# Flasche_v1.net
KiCad netlist of a schematic drawn in EAGLE
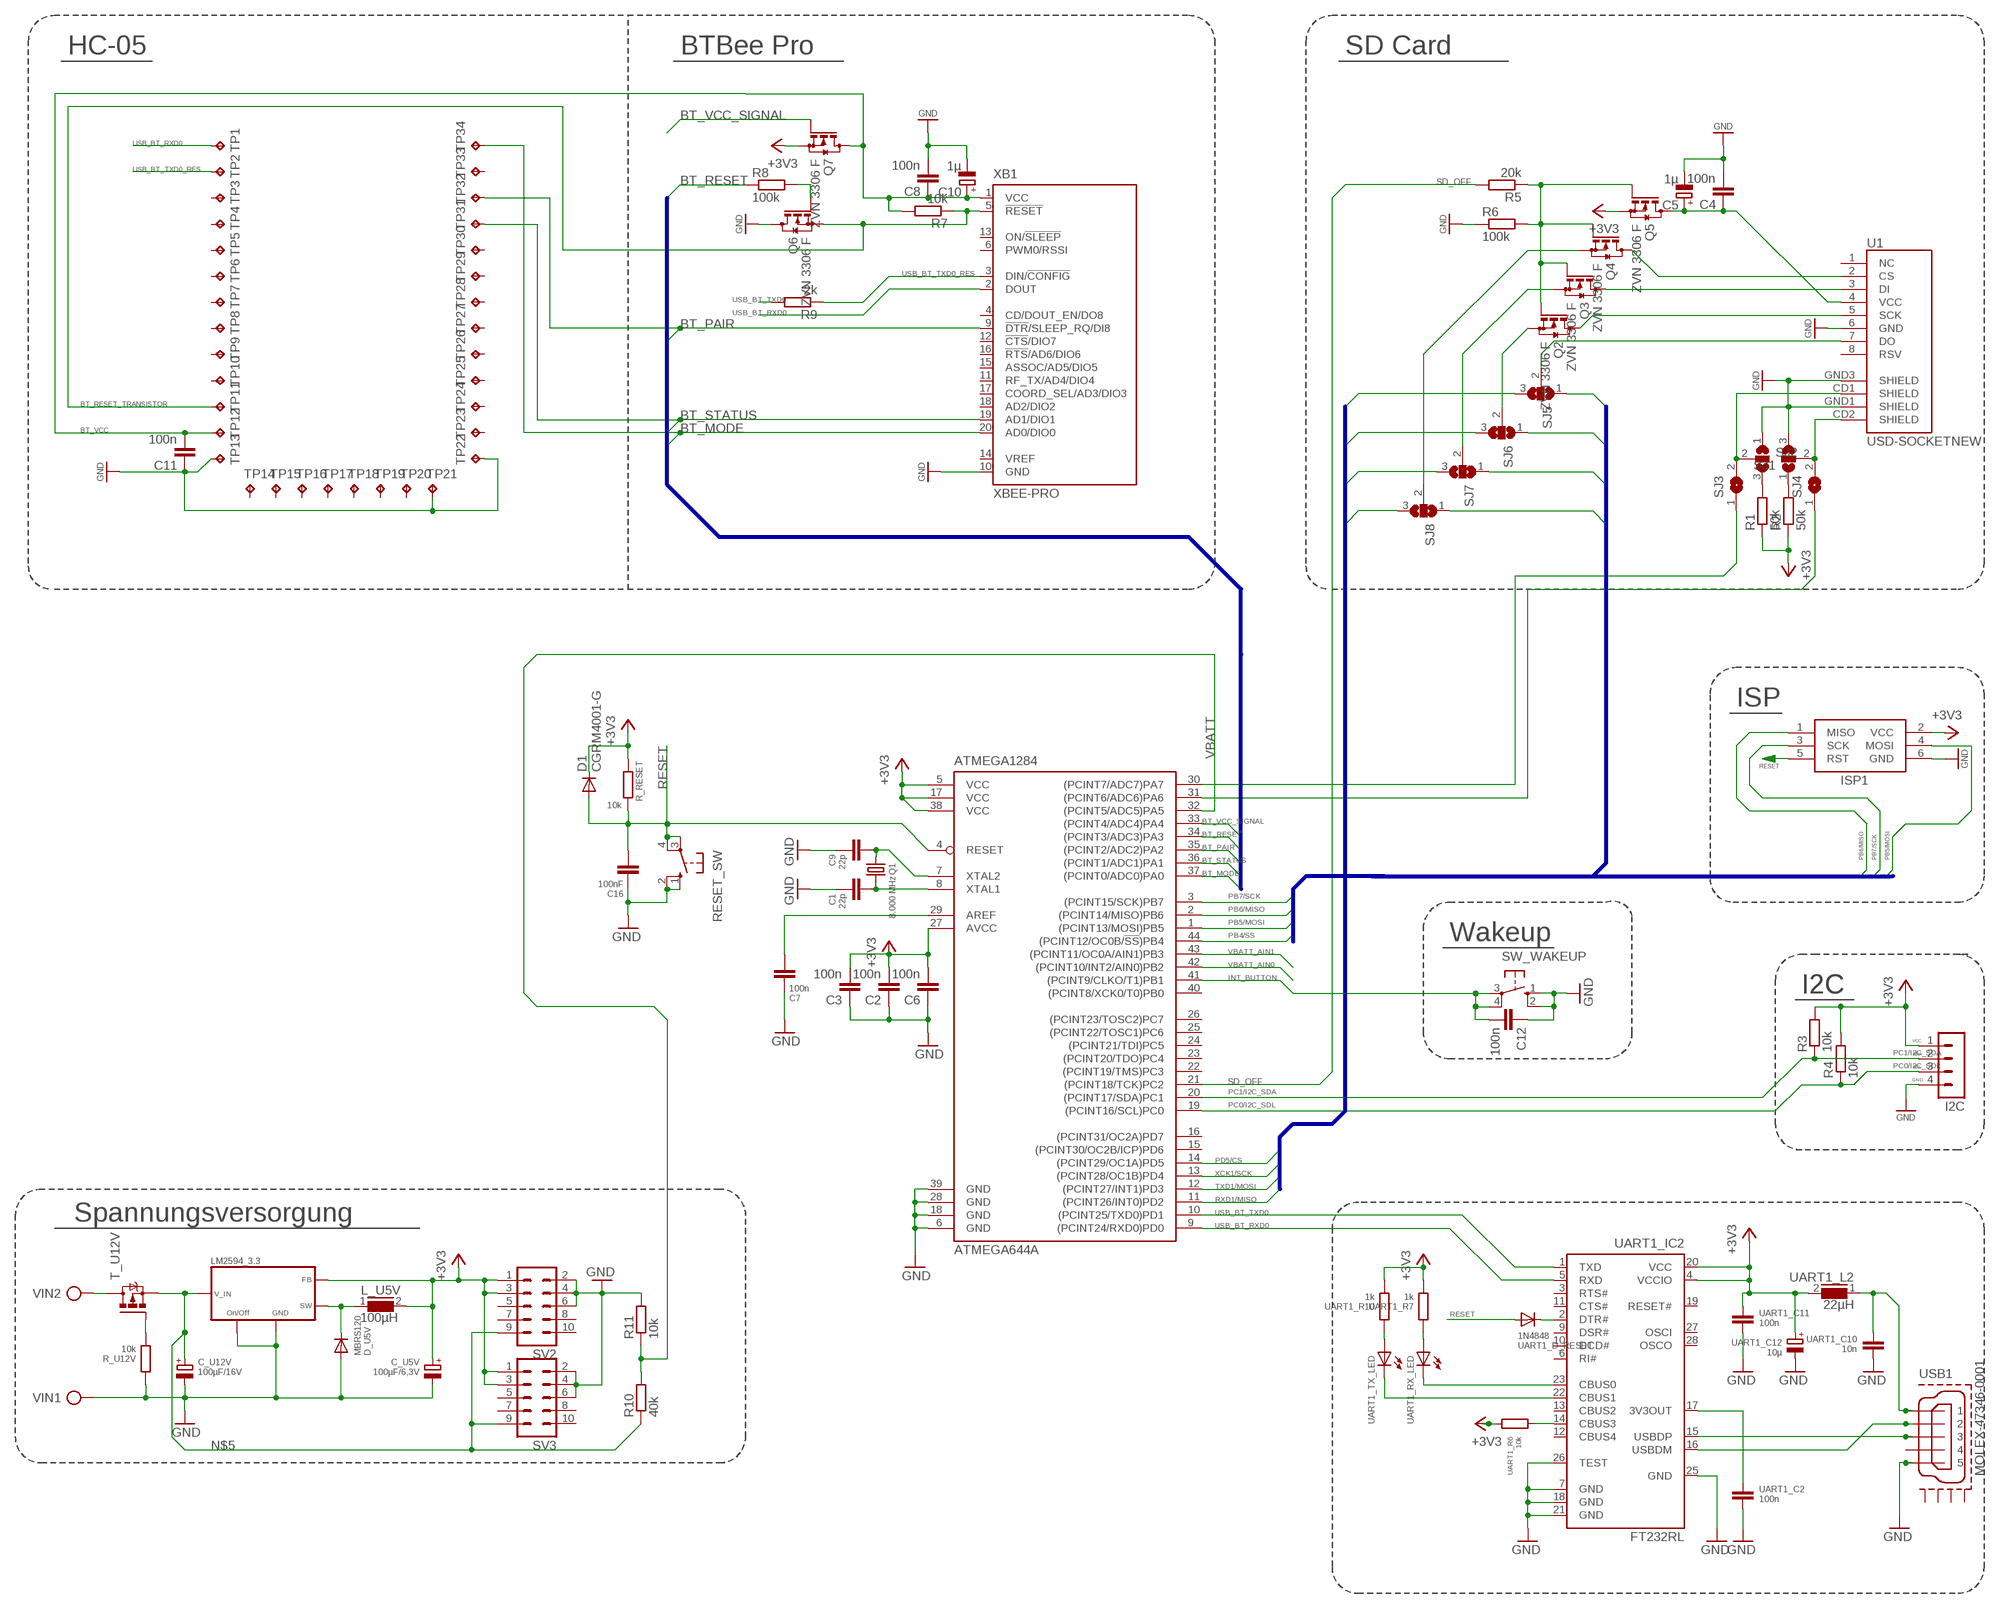
[diagram p0: schematic, sheet 1]

(export (version "E")
  (design (tool "Eeschema 10.0.6"))
  (components
    (comp (ref "ATMEGA1284")
      (value "ATMEGA644A")
      (footprint "eagle-import:TQFP44")
      (fields (field (name "MPN") "ATMEGA644PV-10AU"))
      (libsource (lib "eagle-import") (part "ATMEGA644A"))
    )
    (comp (ref "C1")
      (value "22p")
      (footprint "eagle-import:C0805")
      (libsource (lib "eagle-import") (part "C-0805"))
    )
    (comp (ref "C2")
      (value "100n")
      (footprint "eagle-import:C0805")
      (libsource (lib "eagle-import") (part "C-0805"))
    )
    (comp (ref "C3")
      (value "100n")
      (footprint "eagle-import:C0805")
      (libsource (lib "eagle-import") (part "C-0805"))
    )
    (comp (ref "C4")
      (value "100n")
      (footprint "eagle-import:C0805")
      (libsource (lib "eagle-import") (part "C-0805"))
    )
    (comp (ref "C5")
      (value "1µ")
      (footprint "eagle-import:SMC_D")
      (libsource (lib "eagle-import") (part "rcl_CPOL-EUSMCD"))
    )
    (comp (ref "C6")
      (value "100n")
      (footprint "eagle-import:C0805")
      (libsource (lib "eagle-import") (part "C-0805"))
    )
    (comp (ref "C7")
      (value "100n")
      (footprint "eagle-import:C0805")
      (libsource (lib "eagle-import") (part "C-0805"))
    )
    (comp (ref "C8")
      (value "100n")
      (footprint "eagle-import:C0805")
      (libsource (lib "eagle-import") (part "C-0805"))
    )
    (comp (ref "C9")
      (value "22p")
      (footprint "eagle-import:C0805")
      (libsource (lib "eagle-import") (part "C-0805"))
    )
    (comp (ref "C10")
      (value "1µ")
      (footprint "eagle-import:SMC_D")
      (libsource (lib "eagle-import") (part "rcl_CPOL-EUSMCD"))
    )
    (comp (ref "C11")
      (value "100n")
      (footprint "eagle-import:C0805")
      (libsource (lib "eagle-import") (part "C-0805"))
    )
    (comp (ref "C12")
      (value "100n")
      (footprint "eagle-import:C0805")
      (libsource (lib "eagle-import") (part "C-0805"))
    )
    (comp (ref "C16")
      (value "100nF")
      (footprint "eagle-import:C0805")
      (libsource (lib "eagle-import") (part "C-0805"))
    )
    (comp (ref "C_U5V")
      (value "100µF/6,3V")
      (footprint "eagle-import:SMC_D")
      (libsource (lib "eagle-import") (part "CPOL-EUSMCD"))
    )
    (comp (ref "C_U12V")
      (value "100µF/16V")
      (footprint "eagle-import:SMC_D")
      (libsource (lib "eagle-import") (part "CPOL-EUSMCD"))
    )
    (comp (ref "D1")
      (value "CGRM4001-G")
      (footprint "eagle-import:SOD-123_MINI-SMA")
      (libsource (lib "eagle-import") (part "CGRM400-G1"))
    )
    (comp (ref "D_U5V")
      (value "MBRS120")
      (footprint "eagle-import:SMB")
      (libsource (lib "eagle-import") (part "D_SMB"))
    )
    (comp (ref "I2C")
      (value "MA04-1")
      (footprint "eagle-import:MA04-1")
      (libsource (lib "eagle-import") (part "MA04-1"))
    )
    (comp (ref "ISP1")
      (value "AVRISP-6")
      (footprint "eagle-import:AVRISP")
      (libsource (lib "eagle-import") (part "AVRISP-6"))
    )
    (comp (ref "LM2594_3.3")
      (value "LM2594")
      (footprint "eagle-import:SO08")
      (libsource (lib "eagle-import") (part "LM2594"))
    )
    (comp (ref "L_U5V")
      (value "100µH")
      (footprint "eagle-import:PISM")
      (libsource (lib "eagle-import") (part "L_PISM"))
    )
    (comp (ref "Q1")
      (value "8.000 MHz")
      (footprint "eagle-import:HC18U-V")
      (libsource (lib "eagle-import") (part "CRYSTALHC18U-V"))
    )
    (comp (ref "Q2")
      (value "ZVN 3306 F")
      (footprint "eagle-import:SOT23")
      (libsource (lib "eagle-import") (part "BSS123"))
    )
    (comp (ref "Q3")
      (value "ZVN 3306 F")
      (footprint "eagle-import:SOT23")
      (libsource (lib "eagle-import") (part "BSS123"))
    )
    (comp (ref "Q4")
      (value "ZVN 3306 F")
      (footprint "eagle-import:SOT23")
      (libsource (lib "eagle-import") (part "BSS123"))
    )
    (comp (ref "Q5")
      (value "ZVN 3306 F")
      (footprint "eagle-import:SOT23")
      (libsource (lib "eagle-import") (part "BSS123"))
    )
    (comp (ref "Q6")
      (value "ZVN 3306 F")
      (footprint "eagle-import:SOT23")
      (libsource (lib "eagle-import") (part "BSS123"))
    )
    (comp (ref "Q7")
      (value "ZVN 3306 F")
      (footprint "eagle-import:SOT23")
      (libsource (lib "eagle-import") (part "BSS123"))
    )
    (comp (ref "R1")
      (value "50k")
      (footprint "eagle-import:M1206")
      (libsource (lib "eagle-import") (part "R-EU_M1206"))
    )
    (comp (ref "R2")
      (value "50k")
      (footprint "eagle-import:M1206")
      (libsource (lib "eagle-import") (part "R-EU_M1206"))
    )
    (comp (ref "R3")
      (value "10k")
      (footprint "eagle-import:M1206")
      (libsource (lib "eagle-import") (part "R-EU_M1206"))
    )
    (comp (ref "R4")
      (value "10k")
      (footprint "eagle-import:M1206")
      (libsource (lib "eagle-import") (part "R-EU_M1206"))
    )
    (comp (ref "R5")
      (value "20k")
      (footprint "eagle-import:M1206")
      (libsource (lib "eagle-import") (part "R-EU_M1206"))
    )
    (comp (ref "R6")
      (value "100k")
      (footprint "eagle-import:M1206")
      (libsource (lib "eagle-import") (part "R-EU_M1206"))
    )
    (comp (ref "R7")
      (value "10k")
      (footprint "eagle-import:M1206")
      (libsource (lib "eagle-import") (part "R-EU_M1206"))
    )
    (comp (ref "R8")
      (value "100k")
      (footprint "eagle-import:M1206")
      (libsource (lib "eagle-import") (part "R-EU_M1206"))
    )
    (comp (ref "R9")
      (value "2k")
      (footprint "eagle-import:M1206")
      (libsource (lib "eagle-import") (part "R-EU_M1206"))
    )
    (comp (ref "R10")
      (value "40k")
      (footprint "eagle-import:M1206")
      (libsource (lib "eagle-import") (part "R-EU_M1206"))
    )
    (comp (ref "R11")
      (value "10k")
      (footprint "eagle-import:M1206")
      (libsource (lib "eagle-import") (part "R-EU_M1206"))
    )
    (comp (ref "RESET_SW")
      (value "10-XX")
      (footprint "eagle-import:B3F-10XX")
      (fields (field (name "MPN") "B3F-1000"))
      (libsource (lib "eagle-import") (part "10-XX"))
    )
    (comp (ref "R_RESET")
      (value "10k")
      (footprint "eagle-import:R0805")
      (libsource (lib "eagle-import") (part "R-R0805"))
    )
    (comp (ref "R_U12V")
      (value "10k")
      (footprint "eagle-import:R0805")
      (libsource (lib "eagle-import") (part "R-R0805"))
    )
    (comp (ref "SJ1")
      (value "SJ2W")
      (footprint "eagle-import:SJ_2")
      (libsource (lib "eagle-import") (part "SJ2W"))
    )
    (comp (ref "SJ2")
      (value "SJ2W")
      (footprint "eagle-import:SJ_2")
      (libsource (lib "eagle-import") (part "SJ2W"))
    )
    (comp (ref "SJ3") (value "SJ") (footprint "eagle-import:SJ") (libsource (lib "eagle-import") (part "SJ")))
    (comp (ref "SJ4") (value "SJ") (footprint "eagle-import:SJ") (libsource (lib "eagle-import") (part "SJ")))
    (comp (ref "SJ5")
      (value "SJ2W")
      (footprint "eagle-import:SJ_2")
      (libsource (lib "eagle-import") (part "SJ2W"))
    )
    (comp (ref "SJ6")
      (value "SJ2W")
      (footprint "eagle-import:SJ_2")
      (libsource (lib "eagle-import") (part "SJ2W"))
    )
    (comp (ref "SJ7")
      (value "SJ2W")
      (footprint "eagle-import:SJ_2")
      (libsource (lib "eagle-import") (part "SJ2W"))
    )
    (comp (ref "SJ8")
      (value "SJ2W")
      (footprint "eagle-import:SJ_2")
      (libsource (lib "eagle-import") (part "SJ2W"))
    )
    (comp (ref "SV2")
      (value "ML10L")
      (footprint "eagle-import:ML10L")
      (libsource (lib "eagle-import") (part "ML10L"))
    )
    (comp (ref "SV3")
      (value "ML10L")
      (footprint "eagle-import:ML10L")
      (libsource (lib "eagle-import") (part "ML10L"))
    )
    (comp (ref "SW_WAKEUP")
      (value "10-XX")
      (footprint "eagle-import:B3F-10XX")
      (fields (field (name "MPN") "B3F-1000"))
      (libsource (lib "eagle-import") (part "10-XX"))
    )
    (comp (ref "TP1")
      (value "TPTP06SQ")
      (footprint "eagle-import:TP06SQ")
      (libsource (lib "eagle-import") (part "TPTP06SQ"))
    )
    (comp (ref "TP2")
      (value "TPTP06SQ")
      (footprint "eagle-import:TP06SQ")
      (libsource (lib "eagle-import") (part "TPTP06SQ"))
    )
    (comp (ref "TP3")
      (value "TPTP06SQ")
      (footprint "eagle-import:TP06SQ")
      (libsource (lib "eagle-import") (part "TPTP06SQ"))
    )
    (comp (ref "TP4")
      (value "TPTP06SQ")
      (footprint "eagle-import:TP06SQ")
      (libsource (lib "eagle-import") (part "TPTP06SQ"))
    )
    (comp (ref "TP5")
      (value "TPTP06SQ")
      (footprint "eagle-import:TP06SQ")
      (libsource (lib "eagle-import") (part "TPTP06SQ"))
    )
    (comp (ref "TP6")
      (value "TPTP06SQ")
      (footprint "eagle-import:TP06SQ")
      (libsource (lib "eagle-import") (part "TPTP06SQ"))
    )
    (comp (ref "TP7")
      (value "TPTP06SQ")
      (footprint "eagle-import:TP06SQ")
      (libsource (lib "eagle-import") (part "TPTP06SQ"))
    )
    (comp (ref "TP8")
      (value "TPTP06SQ")
      (footprint "eagle-import:TP06SQ")
      (libsource (lib "eagle-import") (part "TPTP06SQ"))
    )
    (comp (ref "TP9")
      (value "TPTP06SQ")
      (footprint "eagle-import:TP06SQ")
      (libsource (lib "eagle-import") (part "TPTP06SQ"))
    )
    (comp (ref "TP10")
      (value "TPTP06SQ")
      (footprint "eagle-import:TP06SQ")
      (libsource (lib "eagle-import") (part "TPTP06SQ"))
    )
    (comp (ref "TP11")
      (value "TPTP06SQ")
      (footprint "eagle-import:TP06SQ")
      (libsource (lib "eagle-import") (part "TPTP06SQ"))
    )
    (comp (ref "TP12")
      (value "TPTP06SQ")
      (footprint "eagle-import:TP06SQ")
      (libsource (lib "eagle-import") (part "TPTP06SQ"))
    )
    (comp (ref "TP13")
      (value "TPTP06SQ")
      (footprint "eagle-import:TP06SQ")
      (libsource (lib "eagle-import") (part "TPTP06SQ"))
    )
    (comp (ref "TP14")
      (value "TPTP06SQ")
      (footprint "eagle-import:TP06SQ")
      (libsource (lib "eagle-import") (part "TPTP06SQ"))
    )
    (comp (ref "TP15")
      (value "TPTP06SQ")
      (footprint "eagle-import:TP06SQ")
      (libsource (lib "eagle-import") (part "TPTP06SQ"))
    )
    (comp (ref "TP16")
      (value "TPTP06SQ")
      (footprint "eagle-import:TP06SQ")
      (libsource (lib "eagle-import") (part "TPTP06SQ"))
    )
    (comp (ref "TP17")
      (value "TPTP06SQ")
      (footprint "eagle-import:TP06SQ")
      (libsource (lib "eagle-import") (part "TPTP06SQ"))
    )
    (comp (ref "TP18")
      (value "TPTP06SQ")
      (footprint "eagle-import:TP06SQ")
      (libsource (lib "eagle-import") (part "TPTP06SQ"))
    )
    (comp (ref "TP19")
      (value "TPTP06SQ")
      (footprint "eagle-import:TP06SQ")
      (libsource (lib "eagle-import") (part "TPTP06SQ"))
    )
    (comp (ref "TP20")
      (value "TPTP06SQ")
      (footprint "eagle-import:TP06SQ")
      (libsource (lib "eagle-import") (part "TPTP06SQ"))
    )
    (comp (ref "TP21")
      (value "TPTP06SQ")
      (footprint "eagle-import:TP06SQ")
      (libsource (lib "eagle-import") (part "TPTP06SQ"))
    )
    (comp (ref "TP22")
      (value "TPTP06SQ")
      (footprint "eagle-import:TP06SQ")
      (libsource (lib "eagle-import") (part "TPTP06SQ"))
    )
    (comp (ref "TP23")
      (value "TPTP06SQ")
      (footprint "eagle-import:TP06SQ")
      (libsource (lib "eagle-import") (part "TPTP06SQ"))
    )
    (comp (ref "TP24")
      (value "TPTP06SQ")
      (footprint "eagle-import:TP06SQ")
      (libsource (lib "eagle-import") (part "TPTP06SQ"))
    )
    (comp (ref "TP25")
      (value "TPTP06SQ")
      (footprint "eagle-import:TP06SQ")
      (libsource (lib "eagle-import") (part "TPTP06SQ"))
    )
    (comp (ref "TP26")
      (value "TPTP06SQ")
      (footprint "eagle-import:TP06SQ")
      (libsource (lib "eagle-import") (part "TPTP06SQ"))
    )
    (comp (ref "TP27")
      (value "TPTP06SQ")
      (footprint "eagle-import:TP06SQ")
      (libsource (lib "eagle-import") (part "TPTP06SQ"))
    )
    (comp (ref "TP28")
      (value "TPTP06SQ")
      (footprint "eagle-import:TP06SQ")
      (libsource (lib "eagle-import") (part "TPTP06SQ"))
    )
    (comp (ref "TP29")
      (value "TPTP06SQ")
      (footprint "eagle-import:TP06SQ")
      (libsource (lib "eagle-import") (part "TPTP06SQ"))
    )
    (comp (ref "TP30")
      (value "TPTP06SQ")
      (footprint "eagle-import:TP06SQ")
      (libsource (lib "eagle-import") (part "TPTP06SQ"))
    )
    (comp (ref "TP31")
      (value "TPTP06SQ")
      (footprint "eagle-import:TP06SQ")
      (libsource (lib "eagle-import") (part "TPTP06SQ"))
    )
    (comp (ref "TP32")
      (value "TPTP06SQ")
      (footprint "eagle-import:TP06SQ")
      (libsource (lib "eagle-import") (part "TPTP06SQ"))
    )
    (comp (ref "TP33")
      (value "TPTP06SQ")
      (footprint "eagle-import:TP06SQ")
      (libsource (lib "eagle-import") (part "TPTP06SQ"))
    )
    (comp (ref "TP34")
      (value "TPTP06SQ")
      (footprint "eagle-import:TP06SQ")
      (libsource (lib "eagle-import") (part "TPTP06SQ"))
    )
    (comp (ref "T_U12V")
      (value "MOS_P_SOT23_GDS")
      (footprint "eagle-import:SOT23")
      (libsource (lib "eagle-import") (part "MOS_P_SOT23_GDS"))
    )
    (comp (ref "U1")
      (value "USD-SOCKETNEW")
      (footprint "eagle-import:MICRO-SD-SOCKET-PP")
      (libsource (lib "eagle-import") (part "USD-SOCKETNEW"))
    )
    (comp (ref "UART1_C2")
      (value "100n")
      (footprint "eagle-import:C0805")
      (libsource (lib "eagle-import") (part "C-EUC0805"))
    )
    (comp (ref "UART1_C10")
      (value "10n")
      (footprint "eagle-import:C0805")
      (libsource (lib "eagle-import") (part "C-EUC0805"))
    )
    (comp (ref "UART1_C11")
      (value "100n")
      (footprint "eagle-import:C0805")
      (libsource (lib "eagle-import") (part "C-EUC0805"))
    )
    (comp (ref "UART1_C12")
      (value "10µ")
      (footprint "eagle-import:SMC_D")
      (libsource (lib "eagle-import") (part "CPOL-EUSMCD"))
    )
    (comp (ref "UART1_D_RESET")
      (value "1N4848")
      (footprint "eagle-import:MINIMELF")
      (libsource (lib "eagle-import") (part "D_MINIMELF"))
    )
    (comp (ref "UART1_IC2")
      (value "FT232RL")
      (footprint "eagle-import:SSOP28")
      (libsource (lib "eagle-import") (part "FT232RL"))
    )
    (comp (ref "UART1_L2")
      (value "22µH")
      (footprint "eagle-import:PIS2408")
      (libsource (lib "eagle-import") (part "L_PIS2408"))
    )
    (comp (ref "UART1_R6")
      (value "10k")
      (footprint "eagle-import:R0805")
      (libsource (lib "eagle-import") (part "R-EU_R0805"))
    )
    (comp (ref "UART1_R7")
      (value "1k")
      (footprint "eagle-import:R0805")
      (libsource (lib "eagle-import") (part "R-R0805"))
    )
    (comp (ref "UART1_R10")
      (value "1k")
      (footprint "eagle-import:R0805")
      (libsource (lib "eagle-import") (part "R-R0805"))
    )
    (comp (ref "UART1_RX_LED")
      (value "LEDCHIPLED_0805")
      (footprint "eagle-import:CHIPLED_0805")
      (libsource (lib "eagle-import") (part "LEDCHIPLED_0805"))
    )
    (comp (ref "UART1_TX_LED")
      (value "LEDCHIPLED_0805")
      (footprint "eagle-import:CHIPLED_0805")
      (libsource (lib "eagle-import") (part "LEDCHIPLED_0805"))
    )
    (comp (ref "USB1")
      (value "MOLEX-47346-0001")
      (footprint "eagle-import:MOLEX-47364-0001")
      (libsource (lib "eagle-import") (part "MOLEX-47346-0001"))
    )
    (comp (ref "VIN")
      (value "AK350/2")
      (footprint "eagle-import:AK350_2")
      (libsource (lib "eagle-import") (part "AK350/2"))
    )
    (comp (ref "XB1")
      (value "XBEE-PRO")
      (footprint "eagle-import:XBEE-PRO")
      (fields (field (name "MPN") "XBP24-AWI-001"))
      (libsource (lib "eagle-import") (part "XBEE-PRO"))
    )
  )
  (nets
    (net (code "1") (name "+3V3") (class "Default")
      (node (ref "ATMEGA1284") (pin "17") (pinfunction "VCC_17") (pintype "power_in"))
      (node (ref "ATMEGA1284") (pin "27") (pinfunction "AVCC_27") (pintype "power_in"))
      (node (ref "ATMEGA1284") (pin "38") (pinfunction "VCC_38") (pintype "power_in"))
      (node (ref "ATMEGA1284") (pin "5") (pinfunction "VCC_5") (pintype "power_in"))
      (node (ref "C2") (pin "2") (pinfunction "2_2") (pintype "passive"))
      (node (ref "C3") (pin "2") (pinfunction "2_2") (pintype "passive"))
      (node (ref "C6") (pin "2") (pinfunction "2_2") (pintype "passive"))
      (node (ref "C_U5V") (pin "+") (pinfunction "+_+") (pintype "passive"))
      (node (ref "D1") (pin "C") (pinfunction "C_C") (pintype "passive"))
      (node (ref "I2C") (pin "1") (pinfunction "1_1") (pintype "passive"))
      (node (ref "ISP1") (pin "2") (pinfunction "VCC_2") (pintype "power_in"))
      (node (ref "LM2594_3.3") (pin "4") (pinfunction "FB_4") (pintype "passive"))
      (node (ref "L_U5V") (pin "2") (pinfunction "2_2") (pintype "passive"))
      (node (ref "Q5") (pin "2") (pinfunction "S_2") (pintype "passive"))
      (node (ref "Q7") (pin "2") (pinfunction "S_2") (pintype "passive"))
      (node (ref "R1") (pin "1") (pinfunction "1_1") (pintype "passive"))
      (node (ref "R2") (pin "1") (pinfunction "1_1") (pintype "passive"))
      (node (ref "R3") (pin "2") (pinfunction "2_2") (pintype "passive"))
      (node (ref "R4") (pin "2") (pinfunction "2_2") (pintype "passive"))
      (node (ref "R_RESET") (pin "2") (pinfunction "2_2") (pintype "passive"))
      (node (ref "SV2") (pin "1") (pinfunction "1_1") (pintype "passive"))
      (node (ref "SV2") (pin "3") (pinfunction "3_3") (pintype "passive"))
      (node (ref "SV3") (pin "1") (pinfunction "1_1") (pintype "passive"))
      (node (ref "SV3") (pin "3") (pinfunction "3_3") (pintype "passive"))
      (node (ref "UART1_C11") (pin "1") (pinfunction "1_1") (pintype "passive"))
      (node (ref "UART1_C12") (pin "+") (pinfunction "+_+") (pintype "passive"))
      (node (ref "UART1_IC2") (pin "20") (pinfunction "VCC_20") (pintype "input"))
      (node (ref "UART1_IC2") (pin "4") (pinfunction "VCCIO_4") (pintype "input"))
      (node (ref "UART1_L2") (pin "2") (pinfunction "2_2") (pintype "passive"))
      (node (ref "UART1_R10") (pin "1") (pinfunction "1_1") (pintype "passive"))
      (node (ref "UART1_R6") (pin "2") (pinfunction "2_2") (pintype "passive"))
      (node (ref "UART1_R7") (pin "1") (pinfunction "1_1") (pintype "passive"))
    )
    (net (code "2") (name "/BT_MODE") (class "Default")
      (node (ref "ATMEGA1284") (pin "37") (pinfunction "(PCINT0/ADC0)PA0_37") (pintype "bidirectional"))
      (node (ref "TP34") (pin "TP") (pinfunction "TP_TP") (pintype "input"))
      (node (ref "XB1") (pin "20") (pinfunction "AD0/DIO0_20") (pintype "bidirectional"))
    )
    (net (code "3") (name "/BT_PAIR") (class "Default")
      (node (ref "ATMEGA1284") (pin "35") (pinfunction "(PCINT2/ADC2)PA2_35") (pintype "bidirectional"))
      (node (ref "TP32") (pin "TP") (pinfunction "TP_TP") (pintype "input"))
      (node (ref "XB1") (pin "9") (pinfunction "~{DTR}/SLEEP_RQ/DI8_9") (pintype "bidirectional"))
    )
    (net (code "4") (name "/BT_RESET") (class "Default")
      (node (ref "ATMEGA1284") (pin "34") (pinfunction "(PCINT3/ADC3)PA3_34") (pintype "bidirectional"))
      (node (ref "R8") (pin "1") (pinfunction "1_1") (pintype "passive"))
    )
    (net (code "5") (name "/BT_RESET_TRANSISTOR") (class "Default")
      (node (ref "Q6") (pin "2") (pinfunction "S_2") (pintype "passive"))
      (node (ref "R7") (pin "1") (pinfunction "1_1") (pintype "passive"))
      (node (ref "TP11") (pin "TP") (pinfunction "TP_TP") (pintype "input"))
      (node (ref "XB1") (pin "5") (pinfunction "~{RESET}_5") (pintype "input"))
    )
    (net (code "6") (name "/BT_STATUS") (class "Default")
      (node (ref "ATMEGA1284") (pin "36") (pinfunction "(PCINT1/ADC1)PA1_36") (pintype "bidirectional"))
      (node (ref "TP31") (pin "TP") (pinfunction "TP_TP") (pintype "input"))
      (node (ref "XB1") (pin "19") (pinfunction "AD1/DIO1_19") (pintype "bidirectional"))
    )
    (net (code "7") (name "/BT_VCC") (class "Default")
      (node (ref "C10") (pin "+") (pinfunction "+_+") (pintype "passive"))
      (node (ref "C11") (pin "2") (pinfunction "2_2") (pintype "passive"))
      (node (ref "C8") (pin "1") (pinfunction "1_1") (pintype "passive"))
      (node (ref "Q7") (pin "3") (pinfunction "D_3") (pintype "passive"))
      (node (ref "R7") (pin "2") (pinfunction "2_2") (pintype "passive"))
      (node (ref "TP12") (pin "TP") (pinfunction "TP_TP") (pintype "input"))
      (node (ref "XB1") (pin "1") (pinfunction "VCC_1") (pintype "power_in"))
    )
    (net (code "8") (name "/BT_VCC_SIGNAL") (class "Default")
      (node (ref "ATMEGA1284") (pin "33") (pinfunction "(PCINT4/ADC4)PA4_33") (pintype "bidirectional"))
      (node (ref "Q7") (pin "1") (pinfunction "G_1") (pintype "passive"))
    )
    (net (code "9") (name "/INT_BUTTON") (class "Default")
      (node (ref "ATMEGA1284") (pin "41") (pinfunction "(PCINT9/CLKO/T1)PB1_41") (pintype "bidirectional"))
      (node (ref "C12") (pin "2") (pinfunction "2_2") (pintype "passive"))
      (node (ref "SW_WAKEUP") (pin "3") (pinfunction "P_3") (pintype "passive"))
      (node (ref "SW_WAKEUP") (pin "4") (pinfunction "P1_4") (pintype "passive"))
    )
    (net (code "10") (name "/N$5") (class "Default")
      (node (ref "C_U12V") (pin "+") (pinfunction "+_+") (pintype "passive"))
      (node (ref "LM2594_3.3") (pin "7") (pinfunction "IN_7") (pintype "power_in"))
      (node (ref "R10") (pin "1") (pinfunction "1_1") (pintype "passive"))
      (node (ref "SV2") (pin "9") (pinfunction "9_9") (pintype "passive"))
      (node (ref "SV3") (pin "9") (pinfunction "9_9") (pintype "passive"))
      (node (ref "T_U12V") (pin "3") (pinfunction "S_3") (pintype "passive"))
    )
    (net (code "11") (name "/PB4{slash}SS") (class "Default")
      (node (ref "ATMEGA1284") (pin "44") (pinfunction "(PCINT12/OC0B/~{SS})PB4_44") (pintype "bidirectional"))
      (node (ref "SJ8") (pin "1") (pinfunction "1_1") (pintype "passive"))
    )
    (net (code "12") (name "/PB5{slash}MOSI") (class "Default")
      (node (ref "ATMEGA1284") (pin "1") (pinfunction "(PCINT13/MOSI)PB5_1") (pintype "bidirectional"))
      (node (ref "ISP1") (pin "4") (pinfunction "MOSI_4") (pintype "output"))
      (node (ref "SJ7") (pin "1") (pinfunction "1_1") (pintype "passive"))
    )
    (net (code "13") (name "/PB6{slash}MISO") (class "Default")
      (node (ref "ATMEGA1284") (pin "2") (pinfunction "(PCINT14/MISO)PB6_2") (pintype "bidirectional"))
      (node (ref "ISP1") (pin "1") (pinfunction "MISO_1") (pintype "input"))
      (node (ref "SJ5") (pin "1") (pinfunction "1_1") (pintype "passive"))
    )
    (net (code "14") (name "/PB7{slash}SCK") (class "Default")
      (node (ref "ATMEGA1284") (pin "3") (pinfunction "(PCINT15/SCK)PB7_3") (pintype "bidirectional"))
      (node (ref "ISP1") (pin "3") (pinfunction "SCK_3") (pintype "output"))
      (node (ref "SJ6") (pin "1") (pinfunction "1_1") (pintype "passive"))
    )
    (net (code "15") (name "/PC0{slash}I2C_SDL") (class "Default")
      (node (ref "ATMEGA1284") (pin "19") (pinfunction "(PCINT16/SCL)PC0_19") (pintype "output"))
      (node (ref "I2C") (pin "3") (pinfunction "3_3") (pintype "passive"))
      (node (ref "R4") (pin "1") (pinfunction "1_1") (pintype "passive"))
    )
    (net (code "16") (name "/PC1{slash}I2C_SDA") (class "Default")
      (node (ref "ATMEGA1284") (pin "20") (pinfunction "(PCINT17/SDA)PC1_20") (pintype "output"))
      (node (ref "I2C") (pin "2") (pinfunction "2_2") (pintype "passive"))
      (node (ref "R3") (pin "1") (pinfunction "1_1") (pintype "passive"))
    )
    (net (code "17") (name "/PD5{slash}CS") (class "Default")
      (node (ref "ATMEGA1284") (pin "14") (pinfunction "(PCINT29/OC1A)PD5_14") (pintype "bidirectional"))
      (node (ref "SJ8") (pin "3") (pinfunction "3_3") (pintype "passive"))
    )
    (net (code "18") (name "/RESET") (class "Default")
      (node (ref "ATMEGA1284") (pin "4") (pinfunction "RESET_4") (pintype "input"))
      (node (ref "C16") (pin "2") (pinfunction "2_2") (pintype "passive"))
      (node (ref "D1") (pin "A") (pinfunction "A_A") (pintype "passive"))
      (node (ref "ISP1") (pin "5") (pinfunction "RST_5") (pintype "output"))
      (node (ref "RESET_SW") (pin "3") (pinfunction "P_3") (pintype "passive"))
      (node (ref "RESET_SW") (pin "4") (pinfunction "P1_4") (pintype "passive"))
      (node (ref "R_RESET") (pin "1") (pinfunction "1_1") (pintype "passive"))
      (node (ref "UART1_D_RESET") (pin "A") (pinfunction "A_A") (pintype "passive"))
    )
    (net (code "19") (name "/RXD1{slash}MISO") (class "Default")
      (node (ref "ATMEGA1284") (pin "11") (pinfunction "(PCINT26/INT0)PD2_11") (pintype "bidirectional"))
      (node (ref "SJ5") (pin "3") (pinfunction "3_3") (pintype "passive"))
    )
    (net (code "20") (name "/SD_OFF") (class "Default")
      (node (ref "ATMEGA1284") (pin "21") (pinfunction "(PCINT18/TCK)PC2_21") (pintype "output"))
      (node (ref "R5") (pin "2") (pinfunction "2_2") (pintype "passive"))
    )
    (net (code "21") (name "/TXD1{slash}MOSI") (class "Default")
      (node (ref "ATMEGA1284") (pin "12") (pinfunction "(PCINT27/INT1)PD3_12") (pintype "bidirectional"))
      (node (ref "SJ7") (pin "3") (pinfunction "3_3") (pintype "passive"))
    )
    (net (code "22") (name "/USB_BT_RXD0") (class "Default")
      (node (ref "ATMEGA1284") (pin "9") (pinfunction "(PCINT24/RXD0)PD0_9") (pintype "bidirectional"))
      (node (ref "TP1") (pin "TP") (pinfunction "TP_TP") (pintype "input"))
      (node (ref "UART1_IC2") (pin "5") (pinfunction "RXD_5") (pintype "input"))
      (node (ref "XB1") (pin "2") (pinfunction "DOUT_2") (pintype "output"))
    )
    (net (code "23") (name "/USB_BT_TXD0") (class "Default")
      (node (ref "ATMEGA1284") (pin "10") (pinfunction "(PCINT25/TXD0)PD1_10") (pintype "bidirectional"))
      (node (ref "R9") (pin "2") (pinfunction "2_2") (pintype "passive"))
      (node (ref "UART1_IC2") (pin "1") (pinfunction "TXD_1") (pintype "input"))
    )
    (net (code "24") (name "/USB_BT_TXD0_RES") (class "Default")
      (node (ref "R9") (pin "1") (pinfunction "1_1") (pintype "passive"))
      (node (ref "TP2") (pin "TP") (pinfunction "TP_TP") (pintype "input"))
      (node (ref "XB1") (pin "3") (pinfunction "DIN/~{CONFIG}_3") (pintype "input"))
    )
    (net (code "25") (name "/VBATT") (class "Default")
      (node (ref "ATMEGA1284") (pin "32") (pinfunction "(PCINT5/ADC5)PA5_32") (pintype "bidirectional"))
      (node (ref "R10") (pin "2") (pinfunction "2_2") (pintype "passive"))
      (node (ref "R11") (pin "1") (pinfunction "1_1") (pintype "passive"))
    )
    (net (code "26") (name "/VBATT_AIN0") (class "Default")
      (node (ref "ATMEGA1284") (pin "42") (pinfunction "(PCINT10/INT2/AIN0)PB2_42") (pintype "bidirectional"))
    )
    (net (code "27") (name "/VBATT_AIN1") (class "Default")
      (node (ref "ATMEGA1284") (pin "43") (pinfunction "(PCINT11/OC0A/AIN1)PB3_43") (pintype "bidirectional"))
    )
    (net (code "28") (name "/XCK1{slash}SCK") (class "Default")
      (node (ref "ATMEGA1284") (pin "13") (pinfunction "(PCINT28/OC1B)PD4_13") (pintype "bidirectional"))
      (node (ref "SJ6") (pin "3") (pinfunction "3_3") (pintype "passive"))
    )
    (net (code "29") (name "GND") (class "Default")
      (node (ref "ATMEGA1284") (pin "18") (pinfunction "GND_18") (pintype "power_in"))
      (node (ref "ATMEGA1284") (pin "28") (pinfunction "GND_28") (pintype "power_in"))
      (node (ref "ATMEGA1284") (pin "39") (pinfunction "GND_39") (pintype "power_in"))
      (node (ref "ATMEGA1284") (pin "6") (pinfunction "GND_6") (pintype "power_in"))
      (node (ref "C1") (pin "1") (pinfunction "1_1") (pintype "passive"))
      (node (ref "C10") (pin "-") (pinfunction "-_-") (pintype "passive"))
      (node (ref "C11") (pin "1") (pinfunction "1_1") (pintype "passive"))
      (node (ref "C12") (pin "1") (pinfunction "1_1") (pintype "passive"))
      (node (ref "C16") (pin "1") (pinfunction "1_1") (pintype "passive"))
      (node (ref "C2") (pin "1") (pinfunction "1_1") (pintype "passive"))
      (node (ref "C3") (pin "1") (pinfunction "1_1") (pintype "passive"))
      (node (ref "C4") (pin "2") (pinfunction "2_2") (pintype "passive"))
      (node (ref "C5") (pin "-") (pinfunction "-_-") (pintype "passive"))
      (node (ref "C6") (pin "1") (pinfunction "1_1") (pintype "passive"))
      (node (ref "C7") (pin "1") (pinfunction "1_1") (pintype "passive"))
      (node (ref "C8") (pin "2") (pinfunction "2_2") (pintype "passive"))
      (node (ref "C9") (pin "1") (pinfunction "1_1") (pintype "passive"))
      (node (ref "C_U12V") (pin "-") (pinfunction "-_-") (pintype "passive"))
      (node (ref "C_U5V") (pin "-") (pinfunction "-_-") (pintype "passive"))
      (node (ref "D_U5V") (pin "A") (pinfunction "A_A") (pintype "passive"))
      (node (ref "I2C") (pin "4") (pinfunction "4_4") (pintype "passive"))
      (node (ref "ISP1") (pin "6") (pinfunction "GND_6") (pintype "power_in"))
      (node (ref "LM2594_3.3") (pin "5") (pinfunction "ON/OFF_5") (pintype "passive"))
      (node (ref "LM2594_3.3") (pin "6") (pinfunction "GND_6") (pintype "power_in"))
      (node (ref "Q6") (pin "3") (pinfunction "D_3") (pintype "passive"))
      (node (ref "R11") (pin "2") (pinfunction "2_2") (pintype "passive"))
      (node (ref "R6") (pin "1") (pinfunction "1_1") (pintype "passive"))
      (node (ref "RESET_SW") (pin "1") (pinfunction "S_1") (pintype "passive"))
      (node (ref "RESET_SW") (pin "2") (pinfunction "S1_2") (pintype "passive"))
      (node (ref "R_U12V") (pin "2") (pinfunction "2_2") (pintype "passive"))
      (node (ref "SJ1") (pin "3") (pinfunction "3_3") (pintype "passive"))
      (node (ref "SJ2") (pin "1") (pinfunction "1_1") (pintype "passive"))
      (node (ref "SV2") (pin "2") (pinfunction "2_2") (pintype "passive"))
      (node (ref "SV2") (pin "4") (pinfunction "4_4") (pintype "passive"))
      (node (ref "SV2") (pin "6") (pinfunction "6_6") (pintype "passive"))
      (node (ref "SV3") (pin "2") (pinfunction "2_2") (pintype "passive"))
      (node (ref "SV3") (pin "4") (pinfunction "4_4") (pintype "passive"))
      (node (ref "SV3") (pin "6") (pinfunction "6_6") (pintype "passive"))
      (node (ref "SW_WAKEUP") (pin "1") (pinfunction "S_1") (pintype "passive"))
      (node (ref "SW_WAKEUP") (pin "2") (pinfunction "S1_2") (pintype "passive"))
      (node (ref "TP13") (pin "TP") (pinfunction "TP_TP") (pintype "input"))
      (node (ref "TP21") (pin "TP") (pinfunction "TP_TP") (pintype "input"))
      (node (ref "TP22") (pin "TP") (pinfunction "TP_TP") (pintype "input"))
      (node (ref "U1") (pin "6") (pinfunction "GND_6") (pintype "bidirectional"))
      (node (ref "U1") (pin "GND1") (pinfunction "SHIELD_GND1") (pintype "bidirectional"))
      (node (ref "U1") (pin "GND3") (pinfunction "SHIELD_GND3") (pintype "bidirectional"))
      (node (ref "UART1_C10") (pin "2") (pinfunction "2_2") (pintype "passive"))
      (node (ref "UART1_C11") (pin "2") (pinfunction "2_2") (pintype "passive"))
      (node (ref "UART1_C12") (pin "-") (pinfunction "-_-") (pintype "passive"))
      (node (ref "UART1_C2") (pin "2") (pinfunction "2_2") (pintype "passive"))
      (node (ref "UART1_IC2") (pin "18") (pinfunction "GND_18") (pintype "input"))
      (node (ref "UART1_IC2") (pin "21") (pinfunction "GND_21") (pintype "input"))
      (node (ref "UART1_IC2") (pin "25") (pinfunction "GND_25") (pintype "input"))
      (node (ref "UART1_IC2") (pin "26") (pinfunction "TEST_26") (pintype "input"))
      (node (ref "UART1_IC2") (pin "7") (pinfunction "GND_7") (pintype "input"))
      (node (ref "USB1") (pin "5") (pinfunction "5_5") (pintype "input"))
      (node (ref "VIN") (pin "P$1") (pinfunction "KL_P$1") (pintype "passive"))
      (node (ref "XB1") (pin "10") (pinfunction "GND_10") (pintype "power_in"))
    )
    (net (code "30") (name "Net-(ATMEGA1284-(PCINT6{slash}ADC6)PA6)") (class "Default")
      (node (ref "ATMEGA1284") (pin "31") (pinfunction "(PCINT6/ADC6)PA6_31") (pintype "bidirectional"))
      (node (ref "SJ4") (pin "1") (pinfunction "1_1") (pintype "passive"))
    )
    (net (code "31") (name "Net-(ATMEGA1284-(PCINT7{slash}ADC7)PA7)") (class "Default")
      (node (ref "ATMEGA1284") (pin "30") (pinfunction "(PCINT7/ADC7)PA7_30") (pintype "bidirectional"))
      (node (ref "SJ3") (pin "1") (pinfunction "1_1") (pintype "passive"))
    )
    (net (code "32") (name "Net-(ATMEGA1284-AREF)") (class "Default")
      (node (ref "ATMEGA1284") (pin "29") (pinfunction "AREF_29") (pintype "passive"))
      (node (ref "C7") (pin "2") (pinfunction "2_2") (pintype "passive"))
    )
    (net (code "33") (name "Net-(ATMEGA1284-XTAL1)") (class "Default")
      (node (ref "ATMEGA1284") (pin "8") (pinfunction "XTAL1_8") (pintype "bidirectional"))
      (node (ref "C1") (pin "2") (pinfunction "2_2") (pintype "passive"))
      (node (ref "Q1") (pin "1") (pinfunction "1_1") (pintype "passive"))
    )
    (net (code "34") (name "Net-(ATMEGA1284-XTAL2)") (class "Default")
      (node (ref "ATMEGA1284") (pin "7") (pinfunction "XTAL2_7") (pintype "bidirectional"))
      (node (ref "C9") (pin "2") (pinfunction "2_2") (pintype "passive"))
      (node (ref "Q1") (pin "2") (pinfunction "2_2") (pintype "passive"))
    )
    (net (code "35") (name "Net-(LM2594_3.3-SW)") (class "Default")
      (node (ref "D_U5V") (pin "C") (pinfunction "C_C") (pintype "passive"))
      (node (ref "LM2594_3.3") (pin "8") (pinfunction "SW_8") (pintype "passive"))
      (node (ref "L_U5V") (pin "1") (pinfunction "1_1") (pintype "passive"))
    )
    (net (code "36") (name "Net-(Q2-D)") (class "Default")
      (node (ref "Q2") (pin "3") (pinfunction "D_3") (pintype "passive"))
      (node (ref "U1") (pin "5") (pinfunction "SCK_5") (pintype "bidirectional"))
    )
    (net (code "37") (name "Net-(Q2-G)") (class "Default")
      (node (ref "Q2") (pin "1") (pinfunction "G_1") (pintype "passive"))
      (node (ref "Q3") (pin "1") (pinfunction "G_1") (pintype "passive"))
      (node (ref "Q4") (pin "1") (pinfunction "G_1") (pintype "passive"))
      (node (ref "Q5") (pin "1") (pinfunction "G_1") (pintype "passive"))
      (node (ref "R5") (pin "1") (pinfunction "1_1") (pintype "passive"))
      (node (ref "R6") (pin "2") (pinfunction "2_2") (pintype "passive"))
    )
    (net (code "38") (name "Net-(Q2-S)") (class "Default")
      (node (ref "Q2") (pin "2") (pinfunction "S_2") (pintype "passive"))
      (node (ref "SJ6") (pin "2") (pinfunction "2_2") (pintype "passive"))
    )
    (net (code "39") (name "Net-(Q3-D)") (class "Default")
      (node (ref "Q3") (pin "3") (pinfunction "D_3") (pintype "passive"))
      (node (ref "U1") (pin "3") (pinfunction "DI_3") (pintype "bidirectional"))
    )
    (net (code "40") (name "Net-(Q3-S)") (class "Default")
      (node (ref "Q3") (pin "2") (pinfunction "S_2") (pintype "passive"))
      (node (ref "SJ7") (pin "2") (pinfunction "2_2") (pintype "passive"))
    )
    (net (code "41") (name "Net-(Q4-D)") (class "Default")
      (node (ref "Q4") (pin "3") (pinfunction "D_3") (pintype "passive"))
      (node (ref "U1") (pin "2") (pinfunction "CS_2") (pintype "bidirectional"))
    )
    (net (code "42") (name "Net-(Q4-S)") (class "Default")
      (node (ref "Q4") (pin "2") (pinfunction "S_2") (pintype "passive"))
      (node (ref "SJ8") (pin "2") (pinfunction "2_2") (pintype "passive"))
    )
    (net (code "43") (name "Net-(Q5-D)") (class "Default")
      (node (ref "C4") (pin "1") (pinfunction "1_1") (pintype "passive"))
      (node (ref "C5") (pin "+") (pinfunction "+_+") (pintype "passive"))
      (node (ref "Q5") (pin "3") (pinfunction "D_3") (pintype "passive"))
      (node (ref "U1") (pin "4") (pinfunction "VCC_4") (pintype "bidirectional"))
    )
    (net (code "44") (name "Net-(Q6-G)") (class "Default")
      (node (ref "Q6") (pin "1") (pinfunction "G_1") (pintype "passive"))
      (node (ref "R8") (pin "2") (pinfunction "2_2") (pintype "passive"))
    )
    (net (code "45") (name "Net-(R1-Pad2)") (class "Default")
      (node (ref "R1") (pin "2") (pinfunction "2_2") (pintype "passive"))
      (node (ref "SJ2") (pin "3") (pinfunction "3_3") (pintype "passive"))
    )
    (net (code "46") (name "Net-(R2-Pad2)") (class "Default")
      (node (ref "R2") (pin "2") (pinfunction "2_2") (pintype "passive"))
      (node (ref "SJ1") (pin "1") (pinfunction "1_1") (pintype "passive"))
    )
    (net (code "47") (name "Net-(SJ1-Pad2)") (class "Default")
      (node (ref "SJ1") (pin "2") (pinfunction "2_2") (pintype "passive"))
      (node (ref "SJ4") (pin "2") (pinfunction "2_2") (pintype "passive"))
      (node (ref "U1") (pin "CD2") (pinfunction "SHIELD_CD2") (pintype "bidirectional"))
    )
    (net (code "48") (name "Net-(SJ2-Pad2)") (class "Default")
      (node (ref "SJ2") (pin "2") (pinfunction "2_2") (pintype "passive"))
      (node (ref "SJ3") (pin "2") (pinfunction "2_2") (pintype "passive"))
      (node (ref "U1") (pin "CD1") (pinfunction "SHIELD_CD1") (pintype "bidirectional"))
    )
    (net (code "49") (name "Net-(T_U12V-D)") (class "Default")
      (node (ref "T_U12V") (pin "2") (pinfunction "D_2") (pintype "passive"))
      (node (ref "VIN") (pin "P$2") (pinfunction "KL_P$2") (pintype "passive"))
    )
    (net (code "50") (name "Net-(T_U12V-G)") (class "Default")
      (node (ref "R_U12V") (pin "1") (pinfunction "1_1") (pintype "passive"))
      (node (ref "T_U12V") (pin "1") (pinfunction "G_1") (pintype "passive"))
    )
    (net (code "51") (name "Net-(U1-DO)") (class "Default")
      (node (ref "SJ5") (pin "2") (pinfunction "2_2") (pintype "passive"))
      (node (ref "U1") (pin "7") (pinfunction "DO_7") (pintype "bidirectional"))
    )
    (net (code "52") (name "Net-(UART1_C10-Pad1)") (class "Default")
      (node (ref "UART1_C10") (pin "1") (pinfunction "1_1") (pintype "passive"))
      (node (ref "UART1_L2") (pin "1") (pinfunction "1_1") (pintype "passive"))
      (node (ref "USB1") (pin "1") (pinfunction "1_1") (pintype "input"))
    )
    (net (code "53") (name "Net-(UART1_IC2-3V3OUT)") (class "Default")
      (node (ref "UART1_C2") (pin "1") (pinfunction "1_1") (pintype "passive"))
      (node (ref "UART1_IC2") (pin "17") (pinfunction "3V3OUT_17") (pintype "input"))
    )
    (net (code "54") (name "Net-(UART1_IC2-CBUS0)") (class "Default")
      (node (ref "UART1_IC2") (pin "23") (pinfunction "CBUS0_23") (pintype "input"))
      (node (ref "UART1_RX_LED") (pin "C") (pinfunction "C_C") (pintype "passive"))
    )
    (net (code "55") (name "Net-(UART1_IC2-CBUS1)") (class "Default")
      (node (ref "UART1_IC2") (pin "22") (pinfunction "CBUS1_22") (pintype "input"))
      (node (ref "UART1_TX_LED") (pin "C") (pinfunction "C_C") (pintype "passive"))
    )
    (net (code "56") (name "Net-(UART1_IC2-CBUS3)") (class "Default")
      (node (ref "UART1_IC2") (pin "14") (pinfunction "CBUS3_14") (pintype "input"))
      (node (ref "UART1_R6") (pin "1") (pinfunction "1_1") (pintype "passive"))
    )
    (net (code "57") (name "Net-(UART1_IC2-DTR#)") (class "Default")
      (node (ref "UART1_D_RESET") (pin "C") (pinfunction "C_C") (pintype "passive"))
      (node (ref "UART1_IC2") (pin "2") (pinfunction "DTR#_2") (pintype "input"))
    )
    (net (code "58") (name "Net-(UART1_IC2-USBDM)") (class "Default")
      (node (ref "UART1_IC2") (pin "16") (pinfunction "USBDM_16") (pintype "input"))
      (node (ref "USB1") (pin "2") (pinfunction "2_2") (pintype "input"))
    )
    (net (code "59") (name "Net-(UART1_IC2-USBDP)") (class "Default")
      (node (ref "UART1_IC2") (pin "15") (pinfunction "USBDP_15") (pintype "input"))
      (node (ref "USB1") (pin "3") (pinfunction "3_3") (pintype "input"))
    )
    (net (code "60") (name "Net-(UART1_R7-Pad2)") (class "Default")
      (node (ref "UART1_R7") (pin "2") (pinfunction "2_2") (pintype "passive"))
      (node (ref "UART1_RX_LED") (pin "A") (pinfunction "A_A") (pintype "passive"))
    )
    (net (code "61") (name "Net-(UART1_R10-Pad2)") (class "Default")
      (node (ref "UART1_R10") (pin "2") (pinfunction "2_2") (pintype "passive"))
      (node (ref "UART1_TX_LED") (pin "A") (pinfunction "A_A") (pintype "passive"))
    )
    (net (code "62") (name "unconnected-(ATMEGA1284-(PCINT8{slash}XCK0{slash}T0)PB0-Pad40)") (class "Default")
      (node (ref "ATMEGA1284") (pin "40") (pinfunction "(PCINT8/XCK0/T0)PB0_40") (pintype "bidirectional"))
    )
    (net (code "63") (name "unconnected-(ATMEGA1284-(PCINT19{slash}TMS)PC3-Pad22)") (class "Default")
      (node (ref "ATMEGA1284") (pin "22") (pinfunction "(PCINT19/TMS)PC3_22") (pintype "output"))
    )
    (net (code "64") (name "unconnected-(ATMEGA1284-(PCINT20{slash}TDO)PC4-Pad23)") (class "Default")
      (node (ref "ATMEGA1284") (pin "23") (pinfunction "(PCINT20/TDO)PC4_23") (pintype "output"))
    )
    (net (code "65") (name "unconnected-(ATMEGA1284-(PCINT21{slash}TDI)PC5-Pad24)") (class "Default")
      (node (ref "ATMEGA1284") (pin "24") (pinfunction "(PCINT21/TDI)PC5_24") (pintype "output"))
    )
    (net (code "66") (name "unconnected-(ATMEGA1284-(PCINT22{slash}TOSC1)PC6-Pad25)") (class "Default")
      (node (ref "ATMEGA1284") (pin "25") (pinfunction "(PCINT22/TOSC1)PC6_25") (pintype "output"))
    )
    (net (code "67") (name "unconnected-(ATMEGA1284-(PCINT23{slash}TOSC2)PC7-Pad26)") (class "Default")
      (node (ref "ATMEGA1284") (pin "26") (pinfunction "(PCINT23/TOSC2)PC7_26") (pintype "output"))
    )
    (net (code "68") (name "unconnected-(ATMEGA1284-(PCINT30{slash}OC2B{slash}ICP)PD6-Pad15)") (class "Default")
      (node (ref "ATMEGA1284") (pin "15") (pinfunction "(PCINT30/OC2B/ICP)PD6_15") (pintype "bidirectional"))
    )
    (net (code "69") (name "unconnected-(ATMEGA1284-(PCINT31{slash}OC2A)PD7-Pad16)") (class "Default")
      (node (ref "ATMEGA1284") (pin "16") (pinfunction "(PCINT31/OC2A)PD7_16") (pintype "bidirectional"))
    )
    (net (code "70") (name "unconnected-(SV2-Pad5)") (class "Default")
      (node (ref "SV2") (pin "5") (pinfunction "5_5") (pintype "passive"))
    )
    (net (code "71") (name "unconnected-(SV2-Pad7)") (class "Default")
      (node (ref "SV2") (pin "7") (pinfunction "7_7") (pintype "passive"))
    )
    (net (code "72") (name "unconnected-(SV2-Pad8)") (class "Default")
      (node (ref "SV2") (pin "8") (pinfunction "8_8") (pintype "passive"))
    )
    (net (code "73") (name "unconnected-(SV2-Pad10)") (class "Default")
      (node (ref "SV2") (pin "10") (pinfunction "10_10") (pintype "passive"))
    )
    (net (code "74") (name "unconnected-(SV3-Pad5)") (class "Default")
      (node (ref "SV3") (pin "5") (pinfunction "5_5") (pintype "passive"))
    )
    (net (code "75") (name "unconnected-(SV3-Pad7)") (class "Default")
      (node (ref "SV3") (pin "7") (pinfunction "7_7") (pintype "passive"))
    )
    (net (code "76") (name "unconnected-(SV3-Pad8)") (class "Default")
      (node (ref "SV3") (pin "8") (pinfunction "8_8") (pintype "passive"))
    )
    (net (code "77") (name "unconnected-(SV3-Pad10)") (class "Default")
      (node (ref "SV3") (pin "10") (pinfunction "10_10") (pintype "passive"))
    )
    (net (code "78") (name "unconnected-(TP3-PadTP)") (class "Default")
      (node (ref "TP3") (pin "TP") (pinfunction "TP_TP") (pintype "input"))
    )
    (net (code "79") (name "unconnected-(TP4-PadTP)") (class "Default")
      (node (ref "TP4") (pin "TP") (pinfunction "TP_TP") (pintype "input"))
    )
    (net (code "80") (name "unconnected-(TP5-PadTP)") (class "Default")
      (node (ref "TP5") (pin "TP") (pinfunction "TP_TP") (pintype "input"))
    )
    (net (code "81") (name "unconnected-(TP6-PadTP)") (class "Default")
      (node (ref "TP6") (pin "TP") (pinfunction "TP_TP") (pintype "input"))
    )
    (net (code "82") (name "unconnected-(TP7-PadTP)") (class "Default")
      (node (ref "TP7") (pin "TP") (pinfunction "TP_TP") (pintype "input"))
    )
    (net (code "83") (name "unconnected-(TP8-PadTP)") (class "Default")
      (node (ref "TP8") (pin "TP") (pinfunction "TP_TP") (pintype "input"))
    )
    (net (code "84") (name "unconnected-(TP9-PadTP)") (class "Default")
      (node (ref "TP9") (pin "TP") (pinfunction "TP_TP") (pintype "input"))
    )
    (net (code "85") (name "unconnected-(TP10-PadTP)") (class "Default")
      (node (ref "TP10") (pin "TP") (pinfunction "TP_TP") (pintype "input"))
    )
    (net (code "86") (name "unconnected-(TP14-PadTP)") (class "Default")
      (node (ref "TP14") (pin "TP") (pinfunction "TP_TP") (pintype "input"))
    )
    (net (code "87") (name "unconnected-(TP15-PadTP)") (class "Default")
      (node (ref "TP15") (pin "TP") (pinfunction "TP_TP") (pintype "input"))
    )
    (net (code "88") (name "unconnected-(TP16-PadTP)") (class "Default")
      (node (ref "TP16") (pin "TP") (pinfunction "TP_TP") (pintype "input"))
    )
    (net (code "89") (name "unconnected-(TP17-PadTP)") (class "Default")
      (node (ref "TP17") (pin "TP") (pinfunction "TP_TP") (pintype "input"))
    )
    (net (code "90") (name "unconnected-(TP18-PadTP)") (class "Default")
      (node (ref "TP18") (pin "TP") (pinfunction "TP_TP") (pintype "input"))
    )
    (net (code "91") (name "unconnected-(TP19-PadTP)") (class "Default")
      (node (ref "TP19") (pin "TP") (pinfunction "TP_TP") (pintype "input"))
    )
    (net (code "92") (name "unconnected-(TP20-PadTP)") (class "Default")
      (node (ref "TP20") (pin "TP") (pinfunction "TP_TP") (pintype "input"))
    )
    (net (code "93") (name "unconnected-(TP23-PadTP)") (class "Default")
      (node (ref "TP23") (pin "TP") (pinfunction "TP_TP") (pintype "input"))
    )
    (net (code "94") (name "unconnected-(TP24-PadTP)") (class "Default")
      (node (ref "TP24") (pin "TP") (pinfunction "TP_TP") (pintype "input"))
    )
    (net (code "95") (name "unconnected-(TP25-PadTP)") (class "Default")
      (node (ref "TP25") (pin "TP") (pinfunction "TP_TP") (pintype "input"))
    )
    (net (code "96") (name "unconnected-(TP26-PadTP)") (class "Default")
      (node (ref "TP26") (pin "TP") (pinfunction "TP_TP") (pintype "input"))
    )
    (net (code "97") (name "unconnected-(TP27-PadTP)") (class "Default")
      (node (ref "TP27") (pin "TP") (pinfunction "TP_TP") (pintype "input"))
    )
    (net (code "98") (name "unconnected-(TP28-PadTP)") (class "Default")
      (node (ref "TP28") (pin "TP") (pinfunction "TP_TP") (pintype "input"))
    )
    (net (code "99") (name "unconnected-(TP29-PadTP)") (class "Default")
      (node (ref "TP29") (pin "TP") (pinfunction "TP_TP") (pintype "input"))
    )
    (net (code "100") (name "unconnected-(TP30-PadTP)") (class "Default")
      (node (ref "TP30") (pin "TP") (pinfunction "TP_TP") (pintype "input"))
    )
    (net (code "101") (name "unconnected-(TP33-PadTP)") (class "Default")
      (node (ref "TP33") (pin "TP") (pinfunction "TP_TP") (pintype "input"))
    )
    (net (code "102") (name "unconnected-(U1-NC-Pad1)") (class "Default")
      (node (ref "U1") (pin "1") (pinfunction "NC_1") (pintype "bidirectional"))
    )
    (net (code "103") (name "unconnected-(U1-RSV-Pad8)") (class "Default")
      (node (ref "U1") (pin "8") (pinfunction "RSV_8") (pintype "bidirectional"))
    )
    (net (code "104") (name "unconnected-(UART1_IC2-CBUS2-Pad13)") (class "Default")
      (node (ref "UART1_IC2") (pin "13") (pinfunction "CBUS2_13") (pintype "input"))
    )
    (net (code "105") (name "unconnected-(UART1_IC2-CBUS4-Pad12)") (class "Default")
      (node (ref "UART1_IC2") (pin "12") (pinfunction "CBUS4_12") (pintype "input"))
    )
    (net (code "106") (name "unconnected-(UART1_IC2-CTS#-Pad11)") (class "Default")
      (node (ref "UART1_IC2") (pin "11") (pinfunction "CTS#_11") (pintype "input"))
    )
    (net (code "107") (name "unconnected-(UART1_IC2-DCD#-Pad10)") (class "Default")
      (node (ref "UART1_IC2") (pin "10") (pinfunction "DCD#_10") (pintype "input"))
    )
    (net (code "108") (name "unconnected-(UART1_IC2-DSR#-Pad9)") (class "Default")
      (node (ref "UART1_IC2") (pin "9") (pinfunction "DSR#_9") (pintype "input"))
    )
    (net (code "109") (name "unconnected-(UART1_IC2-OSCI-Pad27)") (class "Default")
      (node (ref "UART1_IC2") (pin "27") (pinfunction "OSCI_27") (pintype "input"))
    )
    (net (code "110") (name "unconnected-(UART1_IC2-OSCO-Pad28)") (class "Default")
      (node (ref "UART1_IC2") (pin "28") (pinfunction "OSCO_28") (pintype "input"))
    )
    (net (code "111") (name "unconnected-(UART1_IC2-RESET#-Pad19)") (class "Default")
      (node (ref "UART1_IC2") (pin "19") (pinfunction "RESET#_19") (pintype "input"))
    )
    (net (code "112") (name "unconnected-(UART1_IC2-RI#-Pad6)") (class "Default")
      (node (ref "UART1_IC2") (pin "6") (pinfunction "RI#_6") (pintype "input"))
    )
    (net (code "113") (name "unconnected-(UART1_IC2-RTS#-Pad3)") (class "Default")
      (node (ref "UART1_IC2") (pin "3") (pinfunction "RTS#_3") (pintype "input"))
    )
    (net (code "114") (name "unconnected-(USB1-Pad4)") (class "Default")
      (node (ref "USB1") (pin "4") (pinfunction "4_4") (pintype "input"))
    )
    (net (code "115") (name "unconnected-(USB1-PadGND1)") (class "Default")
      (node (ref "USB1") (pin "GND1") (pinfunction "GND1_GND1") (pintype "bidirectional"))
    )
    (net (code "116") (name "unconnected-(USB1-PadGND2)") (class "Default")
      (node (ref "USB1") (pin "GND2") (pinfunction "GND2_GND2") (pintype "bidirectional"))
    )
    (net (code "117") (name "unconnected-(USB1-PadGND3)") (class "Default")
      (node (ref "USB1") (pin "GND3") (pinfunction "GND3_GND3") (pintype "bidirectional"))
    )
    (net (code "118") (name "unconnected-(USB1-PadGND4)") (class "Default")
      (node (ref "USB1") (pin "GND4") (pinfunction "GND4_GND4") (pintype "bidirectional"))
    )
    (net (code "119") (name "unconnected-(XB1-AD2{slash}DIO2-Pad18)") (class "Default")
      (node (ref "XB1") (pin "18") (pinfunction "AD2/DIO2_18") (pintype "bidirectional"))
    )
    (net (code "120") (name "unconnected-(XB1-ASSOC{slash}AD5{slash}DIO5-Pad15)") (class "Default")
      (node (ref "XB1") (pin "15") (pinfunction "ASSOC/AD5/DIO5_15") (pintype "bidirectional"))
    )
    (net (code "121") (name "unconnected-(XB1-CD{slash}DOUT_EN{slash}DO8-Pad4)") (class "Default")
      (node (ref "XB1") (pin "4") (pinfunction "CD/DOUT_EN/DO8_4") (pintype "output"))
    )
    (net (code "122") (name "unconnected-(XB1-COORD_SEL{slash}AD3{slash}DIO3-Pad17)") (class "Default")
      (node (ref "XB1") (pin "17") (pinfunction "COORD_SEL/AD3/DIO3_17") (pintype "bidirectional"))
    )
    (net (code "123") (name "unconnected-(XB1-ON{slash}~{SLEEP}-Pad13)") (class "Default")
      (node (ref "XB1") (pin "13") (pinfunction "ON/~{SLEEP}_13") (pintype "output"))
    )
    (net (code "124") (name "unconnected-(XB1-PWM0{slash}RSSI-Pad6)") (class "Default")
      (node (ref "XB1") (pin "6") (pinfunction "PWM0/RSSI_6") (pintype "output"))
    )
    (net (code "125") (name "unconnected-(XB1-RF_TX{slash}AD4{slash}DIO4-Pad11)") (class "Default")
      (node (ref "XB1") (pin "11") (pinfunction "RF_TX/AD4/DIO4_11") (pintype "bidirectional"))
    )
    (net (code "126") (name "unconnected-(XB1-VREF-Pad14)") (class "Default")
      (node (ref "XB1") (pin "14") (pinfunction "VREF_14") (pintype "input"))
    )
    (net (code "127") (name "unconnected-(XB1-~{CTS}{slash}DIO7-Pad12)") (class "Default")
      (node (ref "XB1") (pin "12") (pinfunction "~{CTS}/DIO7_12") (pintype "bidirectional"))
    )
    (net (code "128") (name "unconnected-(XB1-~{RTS}{slash}AD6{slash}DIO6-Pad16)") (class "Default")
      (node (ref "XB1") (pin "16") (pinfunction "~{RTS}/AD6/DIO6_16") (pintype "bidirectional"))
    )
  )
)
